# Novo_Container.net
KiCad netlist of a schematic drawn in EAGLE
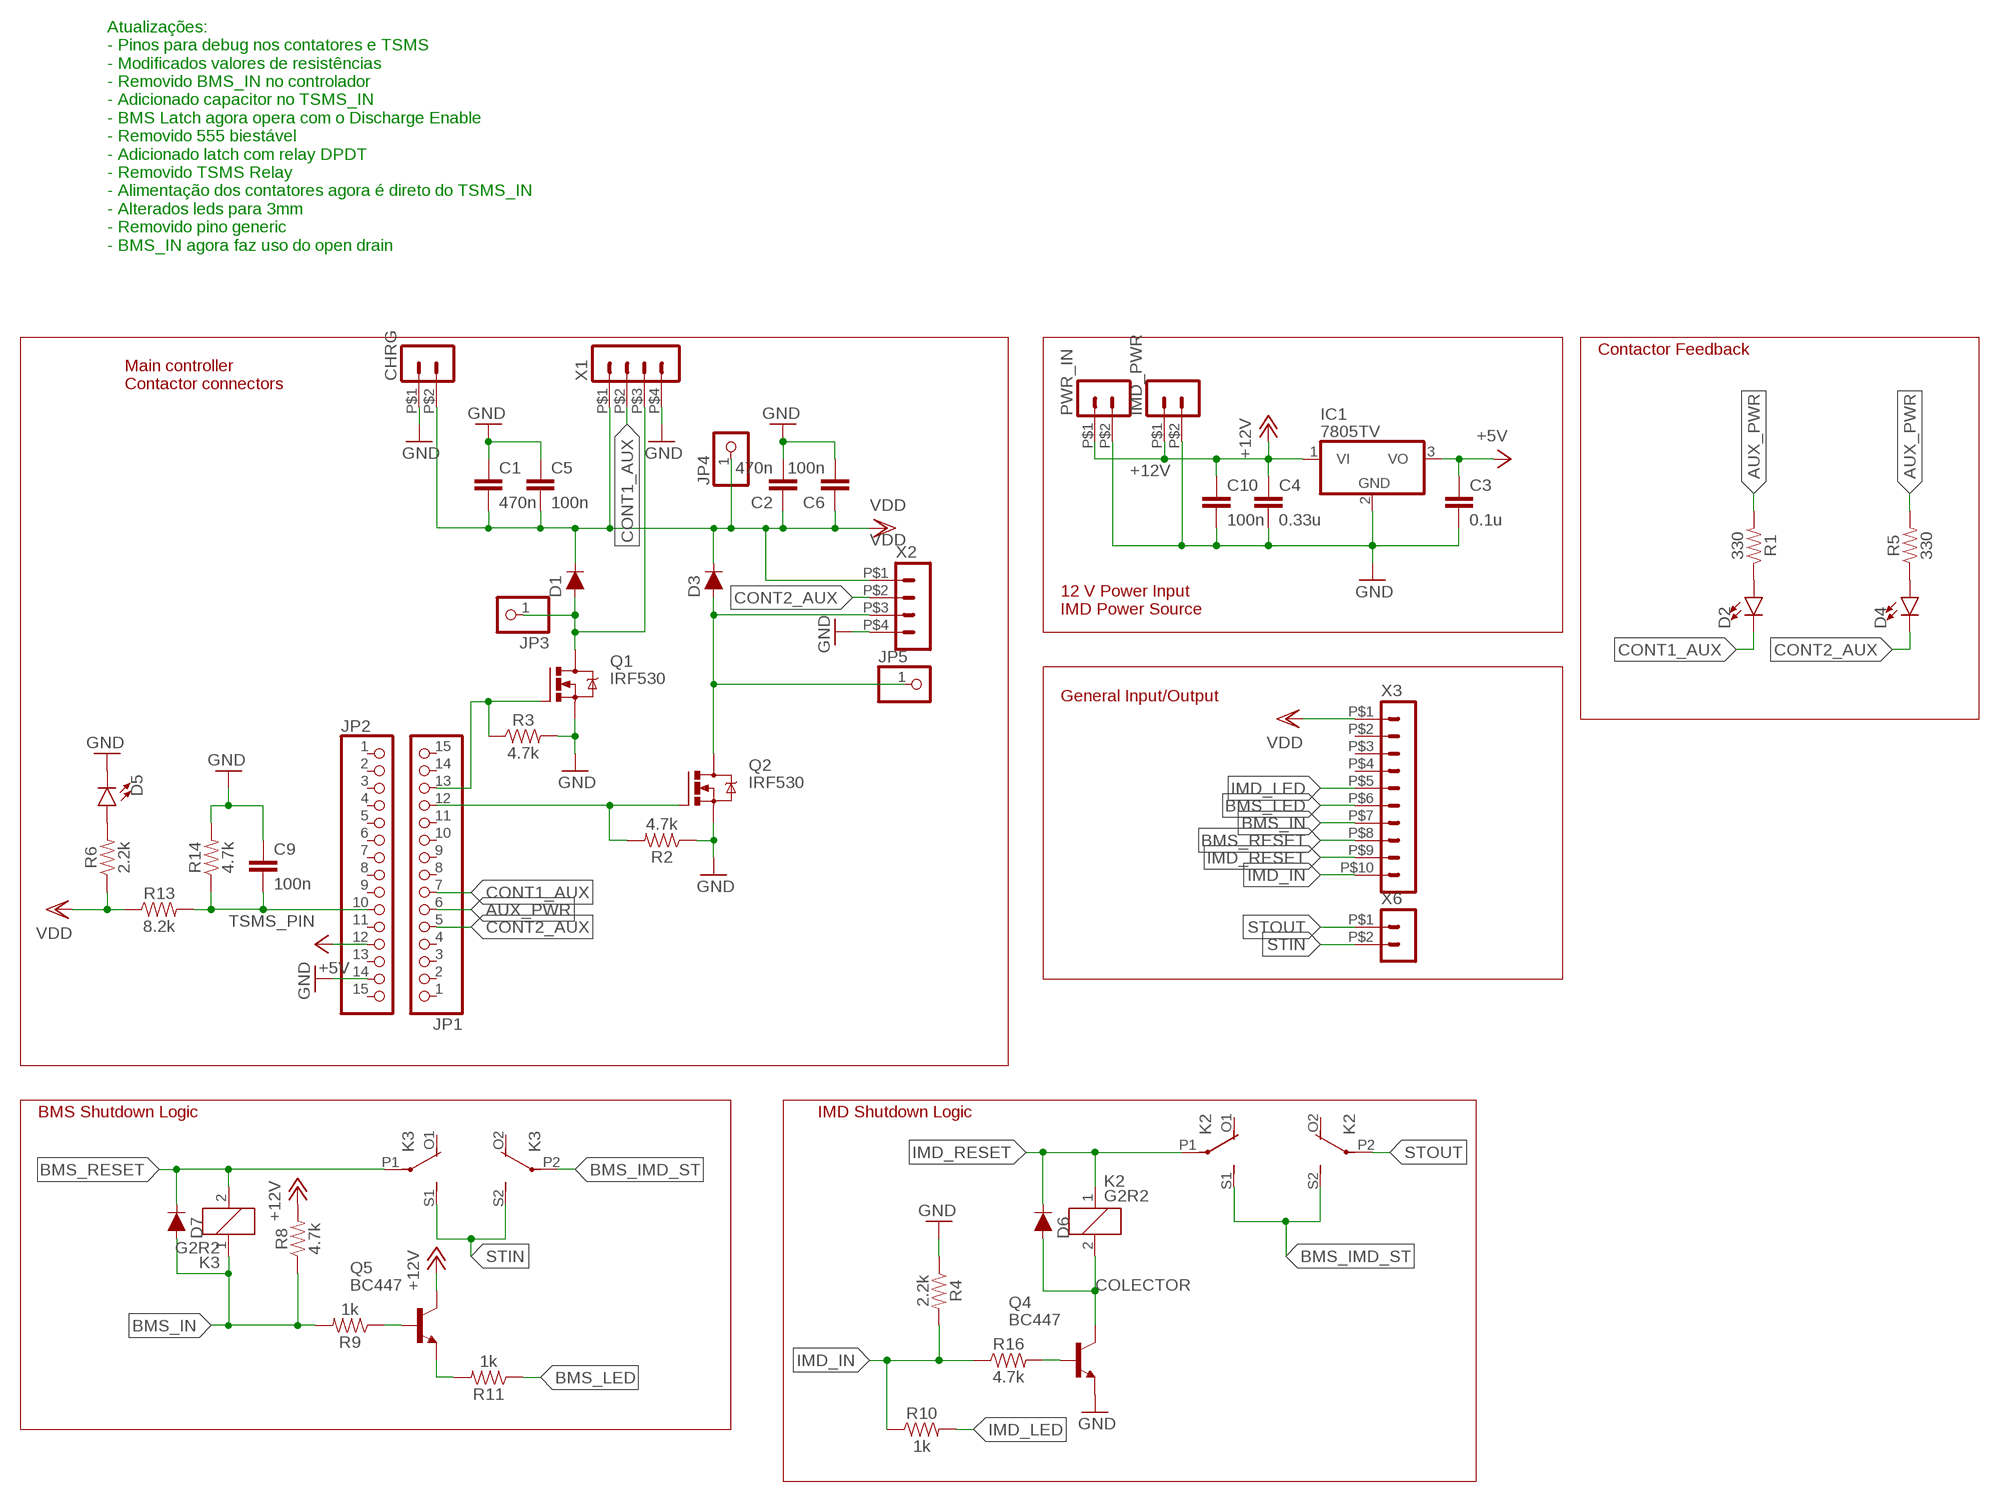
[diagram p0: schematic, sheet 1]

(export (version "E")
  (design (tool "Eeschema 10.0.6"))
  (components
    (comp (ref "C1")
      (value "470n")
      (footprint "eagle-import:C025-025X050")
      (libsource (lib "eagle-import") (part "C-EU025-025X050"))
    )
    (comp (ref "C2")
      (value "470n")
      (footprint "eagle-import:C025-025X050")
      (libsource (lib "eagle-import") (part "C-EU025-025X050"))
    )
    (comp (ref "C3")
      (value "0.1u")
      (footprint "eagle-import:C025-025X050")
      (libsource (lib "eagle-import") (part "C-EU025-025X050"))
    )
    (comp (ref "C4")
      (value "0.33u")
      (footprint "eagle-import:C025-025X050")
      (libsource (lib "eagle-import") (part "C-EU025-025X050"))
    )
    (comp (ref "C5")
      (value "100n")
      (footprint "eagle-import:C025-025X050")
      (libsource (lib "eagle-import") (part "C-EU025-025X050"))
    )
    (comp (ref "C6")
      (value "100n")
      (footprint "eagle-import:C025-025X050")
      (libsource (lib "eagle-import") (part "C-EU025-025X050"))
    )
    (comp (ref "C9")
      (value "100n")
      (footprint "eagle-import:C025-025X050")
      (libsource (lib "eagle-import") (part "C-EU025-025X050"))
    )
    (comp (ref "C10")
      (value "100n")
      (footprint "eagle-import:C025-025X050")
      (libsource (lib "eagle-import") (part "C-EU025-025X050"))
    )
    (comp (ref "CHRG")
      (value "HEADER_POS2_43650-0200")
      (footprint "eagle-import:43650-0200")
      (libsource (lib "eagle-import") (part "HEADER_POS2_?43650-0200"))
    )
    (comp (ref "D1")
      (value "DIODE-1N4148")
      (footprint "eagle-import:DIODE-1N4148")
      (libsource (lib "eagle-import") (part "DIODE-1N4148"))
    )
    (comp (ref "D2")
      (value "LED3MM")
      (footprint "eagle-import:LED_3MM")
      (libsource (lib "eagle-import") (part "LED3MM"))
    )
    (comp (ref "D3")
      (value "DIODE-1N4148")
      (footprint "eagle-import:DIODE-1N4148")
      (libsource (lib "eagle-import") (part "DIODE-1N4148"))
    )
    (comp (ref "D4")
      (value "LED3MM")
      (footprint "eagle-import:LED_3MM")
      (libsource (lib "eagle-import") (part "LED3MM"))
    )
    (comp (ref "D5")
      (value "LED3MM")
      (footprint "eagle-import:LED_3MM")
      (libsource (lib "eagle-import") (part "LED3MM"))
    )
    (comp (ref "D6")
      (value "DIODE-1N4148")
      (footprint "eagle-import:DIODE-1N4148")
      (libsource (lib "eagle-import") (part "DIODE-1N4148"))
    )
    (comp (ref "D7")
      (value "DIODE-1N4148")
      (footprint "eagle-import:DIODE-1N4148")
      (libsource (lib "eagle-import") (part "DIODE-1N4148"))
    )
    (comp (ref "IC1")
      (value "7805TV")
      (footprint "eagle-import:TO220V")
      (libsource (lib "eagle-import") (part "78TV05"))
    )
    (comp (ref "IMD_PWR")
      (value "HEADER_POS2_43650-0200")
      (footprint "eagle-import:43650-0200")
      (libsource (lib "eagle-import") (part "HEADER_POS2_?43650-0200"))
    )
    (comp (ref "JP1")
      (value "PINHD-1X15")
      (footprint "eagle-import:1X15")
      (libsource (lib "eagle-import") (part "PINHD-1X15"))
    )
    (comp (ref "JP2")
      (value "PINHD-1X15")
      (footprint "eagle-import:1X15")
      (libsource (lib "eagle-import") (part "PINHD-1X15"))
    )
    (comp (ref "JP3")
      (value "PINHD-1X1")
      (footprint "eagle-import:1X01")
      (libsource (lib "eagle-import") (part "PINHD-1X1"))
    )
    (comp (ref "JP4")
      (value "PINHD-1X1")
      (footprint "eagle-import:1X01")
      (libsource (lib "eagle-import") (part "PINHD-1X1"))
    )
    (comp (ref "JP5")
      (value "PINHD-1X1")
      (footprint "eagle-import:1X01")
      (libsource (lib "eagle-import") (part "PINHD-1X1"))
    )
    (comp (ref "K2")
      (value "G2R2")
      (footprint "eagle-import:G2R2")
      (fields (field (name "MF") "OMRON COMPONENTS USA") (field (name "MPN") "G2R-2-DC6"))
      (libsource (lib "eagle-import") (part "G2R2"))
    )
    (comp (ref "K3")
      (value "G2R2")
      (footprint "eagle-import:G2R2")
      (fields (field (name "MF") "OMRON COMPONENTS USA") (field (name "MPN") "G2R-2-DC6"))
      (libsource (lib "eagle-import") (part "G2R2"))
    )
    (comp (ref "PWR_IN")
      (value "HEADER_POS2_43650-0200")
      (footprint "eagle-import:43650-0200")
      (libsource (lib "eagle-import") (part "HEADER_POS2_?43650-0200"))
    )
    (comp (ref "Q1")
      (value "IRF530")
      (footprint "eagle-import:TO220BV")
      (libsource (lib "eagle-import") (part "IRF530"))
    )
    (comp (ref "Q2")
      (value "IRF530")
      (footprint "eagle-import:TO220BV")
      (libsource (lib "eagle-import") (part "IRF530"))
    )
    (comp (ref "Q4")
      (value "BC447")
      (footprint "eagle-import:TO92-EBC")
      (libsource (lib "eagle-import") (part "BC447"))
    )
    (comp (ref "Q5")
      (value "BC447")
      (footprint "eagle-import:TO92-EBC")
      (libsource (lib "eagle-import") (part "BC447"))
    )
    (comp (ref "R1")
      (value "330")
      (footprint "eagle-import:AXIAL-0.3")
      (libsource (lib "eagle-import") (part "RESISTORAXIAL-0.3"))
    )
    (comp (ref "R2")
      (value "4.7k")
      (footprint "eagle-import:AXIAL-0.3")
      (libsource (lib "eagle-import") (part "RESISTORAXIAL-0.3"))
    )
    (comp (ref "R3")
      (value "4.7k")
      (footprint "eagle-import:AXIAL-0.3")
      (libsource (lib "eagle-import") (part "RESISTORAXIAL-0.3"))
    )
    (comp (ref "R4")
      (value "2.2k")
      (footprint "eagle-import:AXIAL-0.3")
      (libsource (lib "eagle-import") (part "RESISTORAXIAL-0.3"))
    )
    (comp (ref "R5")
      (value "330")
      (footprint "eagle-import:AXIAL-0.3")
      (libsource (lib "eagle-import") (part "RESISTORAXIAL-0.3"))
    )
    (comp (ref "R6")
      (value "2.2k")
      (footprint "eagle-import:AXIAL-0.3")
      (libsource (lib "eagle-import") (part "RESISTORAXIAL-0.3"))
    )
    (comp (ref "R8")
      (value "4.7k")
      (footprint "eagle-import:AXIAL-0.3")
      (libsource (lib "eagle-import") (part "RESISTORAXIAL-0.3"))
    )
    (comp (ref "R9")
      (value "1k")
      (footprint "eagle-import:AXIAL-0.3")
      (libsource (lib "eagle-import") (part "RESISTORAXIAL-0.3"))
    )
    (comp (ref "R10")
      (value "1k")
      (footprint "eagle-import:AXIAL-0.3")
      (libsource (lib "eagle-import") (part "RESISTORAXIAL-0.3"))
    )
    (comp (ref "R11")
      (value "1k")
      (footprint "eagle-import:AXIAL-0.3")
      (libsource (lib "eagle-import") (part "RESISTORAXIAL-0.3"))
    )
    (comp (ref "R13")
      (value "8.2k")
      (footprint "eagle-import:AXIAL-0.3")
      (libsource (lib "eagle-import") (part "RESISTORAXIAL-0.3"))
    )
    (comp (ref "R14")
      (value "4.7k")
      (footprint "eagle-import:AXIAL-0.3")
      (libsource (lib "eagle-import") (part "RESISTORAXIAL-0.3"))
    )
    (comp (ref "R16")
      (value "4.7k")
      (footprint "eagle-import:AXIAL-0.3")
      (libsource (lib "eagle-import") (part "RESISTORAXIAL-0.3"))
    )
    (comp (ref "X1")
      (value "HEADER_POS4_43045-0401")
      (footprint "eagle-import:43045-0400")
      (libsource (lib "eagle-import") (part "HEADER_POS4_?43045-0401"))
    )
    (comp (ref "X2")
      (value "HEADER_POS4_43045-0401")
      (footprint "eagle-import:43045-0400")
      (libsource (lib "eagle-import") (part "HEADER_POS4_?43045-0401"))
    )
    (comp (ref "X3")
      (value "HEADER_POS10_43045-1000")
      (footprint "eagle-import:43045-1000")
      (libsource (lib "eagle-import") (part "HEADER_POS10_?43045-1000"))
    )
    (comp (ref "X6")
      (value "HEADER_POS2_43650-0200")
      (footprint "eagle-import:43650-0200")
      (libsource (lib "eagle-import") (part "HEADER_POS2_?43650-0200"))
    )
  )
  (nets
    (net (code "1") (name "+5V") (class "Default")
      (node (ref "C3") (pin "1") (pinfunction "1_1") (pintype "passive"))
      (node (ref "IC1") (pin "3") (pinfunction "VO_3") (pintype "passive"))
      (node (ref "JP2") (pin "12") (pinfunction "12_12") (pintype "passive"))
    )
    (net (code "2") (name "+12V") (class "Default")
      (node (ref "C10") (pin "1") (pinfunction "1_1") (pintype "passive"))
      (node (ref "C4") (pin "1") (pinfunction "1_1") (pintype "passive"))
      (node (ref "IC1") (pin "1") (pinfunction "VI_1") (pintype "input"))
      (node (ref "IMD_PWR") (pin "P$1") (pinfunction "1_P$1") (pintype "passive"))
      (node (ref "PWR_IN") (pin "P$1") (pinfunction "1_P$1") (pintype "passive"))
      (node (ref "Q5") (pin "C") (pinfunction "C_C") (pintype "passive"))
      (node (ref "R8") (pin "P$2") (pinfunction "2_P$2") (pintype "passive"))
    )
    (net (code "3") (name "/COLECTOR") (class "Default")
      (node (ref "D6") (pin "A") (pinfunction "A_A") (pintype "passive"))
      (node (ref "K2") (pin "2") (pinfunction "2_2") (pintype "passive"))
      (node (ref "Q4") (pin "C") (pinfunction "C_C") (pintype "passive"))
    )
    (net (code "4") (name "/TSMS_PIN") (class "Default")
      (node (ref "C9") (pin "2") (pinfunction "2_2") (pintype "passive"))
      (node (ref "JP2") (pin "10") (pinfunction "10_10") (pintype "passive"))
      (node (ref "R13") (pin "P$2") (pinfunction "2_P$2") (pintype "passive"))
      (node (ref "R14") (pin "P$1") (pinfunction "1_P$1") (pintype "passive"))
    )
    (net (code "5") (name "AUX_PWR") (class "Default")
      (node (ref "JP1") (pin "6") (pinfunction "6_6") (pintype "passive"))
      (node (ref "R1") (pin "P$2") (pinfunction "2_P$2") (pintype "passive"))
      (node (ref "R5") (pin "P$2") (pinfunction "2_P$2") (pintype "passive"))
    )
    (net (code "6") (name "BMS_IMD_ST") (class "Default")
      (node (ref "K2") (pin "S1") (pinfunction "S_S1") (pintype "passive"))
      (node (ref "K2") (pin "S2") (pinfunction "S_S2") (pintype "passive"))
      (node (ref "K3") (pin "P2") (pinfunction "P_P2") (pintype "passive"))
    )
    (net (code "7") (name "BMS_IN") (class "Default")
      (node (ref "D7") (pin "A") (pinfunction "A_A") (pintype "passive"))
      (node (ref "K3") (pin "1") (pinfunction "1_1") (pintype "passive"))
      (node (ref "R8") (pin "P$1") (pinfunction "1_P$1") (pintype "passive"))
      (node (ref "R9") (pin "P$2") (pinfunction "2_P$2") (pintype "passive"))
      (node (ref "X3") (pin "P$7") (pinfunction "7_P$7") (pintype "passive"))
    )
    (net (code "8") (name "BMS_LED") (class "Default")
      (node (ref "R11") (pin "P$1") (pinfunction "1_P$1") (pintype "passive"))
      (node (ref "X3") (pin "P$6") (pinfunction "6_P$6") (pintype "passive"))
    )
    (net (code "9") (name "BMS_RESET") (class "Default")
      (node (ref "D7") (pin "C") (pinfunction "C_C") (pintype "passive"))
      (node (ref "K3") (pin "2") (pinfunction "2_2") (pintype "passive"))
      (node (ref "K3") (pin "P1") (pinfunction "P_P1") (pintype "passive"))
      (node (ref "X3") (pin "P$8") (pinfunction "8_P$8") (pintype "passive"))
    )
    (net (code "10") (name "CONT1_AUX") (class "Default")
      (node (ref "D2") (pin "K") (pinfunction "C_K") (pintype "passive"))
      (node (ref "JP1") (pin "7") (pinfunction "7_7") (pintype "passive"))
      (node (ref "X1") (pin "P$2") (pinfunction "2_P$2") (pintype "passive"))
    )
    (net (code "11") (name "CONT2_AUX") (class "Default")
      (node (ref "D4") (pin "K") (pinfunction "C_K") (pintype "passive"))
      (node (ref "JP1") (pin "5") (pinfunction "5_5") (pintype "passive"))
      (node (ref "X2") (pin "P$2") (pinfunction "2_P$2") (pintype "passive"))
    )
    (net (code "12") (name "GND") (class "Default")
      (node (ref "C1") (pin "1") (pinfunction "1_1") (pintype "passive"))
      (node (ref "C10") (pin "2") (pinfunction "2_2") (pintype "passive"))
      (node (ref "C2") (pin "2") (pinfunction "2_2") (pintype "passive"))
      (node (ref "C3") (pin "2") (pinfunction "2_2") (pintype "passive"))
      (node (ref "C4") (pin "2") (pinfunction "2_2") (pintype "passive"))
      (node (ref "C5") (pin "1") (pinfunction "1_1") (pintype "passive"))
      (node (ref "C6") (pin "2") (pinfunction "2_2") (pintype "passive"))
      (node (ref "C9") (pin "1") (pinfunction "1_1") (pintype "passive"))
      (node (ref "CHRG") (pin "P$1") (pinfunction "1_P$1") (pintype "passive"))
      (node (ref "D5") (pin "K") (pinfunction "C_K") (pintype "passive"))
      (node (ref "IC1") (pin "2") (pinfunction "GND_2") (pintype "passive"))
      (node (ref "IMD_PWR") (pin "P$2") (pinfunction "2_P$2") (pintype "passive"))
      (node (ref "JP2") (pin "14") (pinfunction "14_14") (pintype "passive"))
      (node (ref "PWR_IN") (pin "P$2") (pinfunction "2_P$2") (pintype "passive"))
      (node (ref "Q1") (pin "S") (pinfunction "S_S") (pintype "passive"))
      (node (ref "Q2") (pin "S") (pinfunction "S_S") (pintype "passive"))
      (node (ref "Q4") (pin "E") (pinfunction "E_E") (pintype "passive"))
      (node (ref "R14") (pin "P$2") (pinfunction "2_P$2") (pintype "passive"))
      (node (ref "R2") (pin "P$1") (pinfunction "1_P$1") (pintype "passive"))
      (node (ref "R3") (pin "P$2") (pinfunction "2_P$2") (pintype "passive"))
      (node (ref "R4") (pin "P$1") (pinfunction "1_P$1") (pintype "passive"))
      (node (ref "X1") (pin "P$4") (pinfunction "4_P$4") (pintype "passive"))
      (node (ref "X2") (pin "P$4") (pinfunction "4_P$4") (pintype "passive"))
    )
    (net (code "13") (name "IMD_IN") (class "Default")
      (node (ref "R10") (pin "P$1") (pinfunction "1_P$1") (pintype "passive"))
      (node (ref "R16") (pin "P$1") (pinfunction "1_P$1") (pintype "passive"))
      (node (ref "R4") (pin "P$2") (pinfunction "2_P$2") (pintype "passive"))
      (node (ref "X3") (pin "P$10") (pinfunction "10_P$10") (pintype "passive"))
    )
    (net (code "14") (name "IMD_LED") (class "Default")
      (node (ref "R10") (pin "P$2") (pinfunction "2_P$2") (pintype "passive"))
      (node (ref "X3") (pin "P$5") (pinfunction "5_P$5") (pintype "passive"))
    )
    (net (code "15") (name "IMD_RESET") (class "Default")
      (node (ref "D6") (pin "C") (pinfunction "C_C") (pintype "passive"))
      (node (ref "K2") (pin "1") (pinfunction "1_1") (pintype "passive"))
      (node (ref "K2") (pin "P1") (pinfunction "P_P1") (pintype "passive"))
      (node (ref "X3") (pin "P$9") (pinfunction "9_P$9") (pintype "passive"))
    )
    (net (code "16") (name "Net-(R1-1)") (class "Default")
      (node (ref "D2") (pin "A") (pinfunction "A_A") (pintype "passive"))
      (node (ref "R1") (pin "P$1") (pinfunction "1_P$1") (pintype "passive"))
    )
    (net (code "17") (name "Net-(R2-2)") (class "Default")
      (node (ref "JP1") (pin "12") (pinfunction "12_12") (pintype "passive"))
      (node (ref "Q2") (pin "G") (pinfunction "G_G") (pintype "passive"))
      (node (ref "R2") (pin "P$2") (pinfunction "2_P$2") (pintype "passive"))
    )
    (net (code "18") (name "Net-(R3-1)") (class "Default")
      (node (ref "JP1") (pin "13") (pinfunction "13_13") (pintype "passive"))
      (node (ref "Q1") (pin "G") (pinfunction "G_G") (pintype "passive"))
      (node (ref "R3") (pin "P$1") (pinfunction "1_P$1") (pintype "passive"))
    )
    (net (code "19") (name "Net-(R5-1)") (class "Default")
      (node (ref "D4") (pin "A") (pinfunction "A_A") (pintype "passive"))
      (node (ref "R5") (pin "P$1") (pinfunction "1_P$1") (pintype "passive"))
    )
    (net (code "20") (name "Net-(R6-2)") (class "Default")
      (node (ref "D5") (pin "A") (pinfunction "A_A") (pintype "passive"))
      (node (ref "R6") (pin "P$2") (pinfunction "2_P$2") (pintype "passive"))
    )
    (net (code "21") (name "Net-(R9-1)") (class "Default")
      (node (ref "Q5") (pin "B") (pinfunction "B_B") (pintype "passive"))
      (node (ref "R9") (pin "P$1") (pinfunction "1_P$1") (pintype "passive"))
    )
    (net (code "22") (name "Net-(R11-2)") (class "Default")
      (node (ref "Q5") (pin "E") (pinfunction "E_E") (pintype "passive"))
      (node (ref "R11") (pin "P$2") (pinfunction "2_P$2") (pintype "passive"))
    )
    (net (code "23") (name "Net-(R16-2)") (class "Default")
      (node (ref "Q4") (pin "B") (pinfunction "B_B") (pintype "passive"))
      (node (ref "R16") (pin "P$2") (pinfunction "2_P$2") (pintype "passive"))
    )
    (net (code "24") (name "Net-(X1-3)") (class "Default")
      (node (ref "D1") (pin "A") (pinfunction "A_A") (pintype "passive"))
      (node (ref "JP3") (pin "1") (pinfunction "1_1") (pintype "passive"))
      (node (ref "Q1") (pin "D") (pinfunction "D_D") (pintype "passive"))
      (node (ref "X1") (pin "P$3") (pinfunction "3_P$3") (pintype "passive"))
    )
    (net (code "25") (name "Net-(X2-3)") (class "Default")
      (node (ref "D3") (pin "A") (pinfunction "A_A") (pintype "passive"))
      (node (ref "JP5") (pin "1") (pinfunction "1_1") (pintype "passive"))
      (node (ref "Q2") (pin "D") (pinfunction "D_D") (pintype "passive"))
      (node (ref "X2") (pin "P$3") (pinfunction "3_P$3") (pintype "passive"))
    )
    (net (code "26") (name "STIN") (class "Default")
      (node (ref "K3") (pin "S1") (pinfunction "S_S1") (pintype "passive"))
      (node (ref "K3") (pin "S2") (pinfunction "S_S2") (pintype "passive"))
      (node (ref "X6") (pin "P$2") (pinfunction "2_P$2") (pintype "passive"))
    )
    (net (code "27") (name "STOUT") (class "Default")
      (node (ref "K2") (pin "P2") (pinfunction "P_P2") (pintype "passive"))
      (node (ref "X6") (pin "P$1") (pinfunction "1_P$1") (pintype "passive"))
    )
    (net (code "28") (name "VDD") (class "Default")
      (node (ref "C1") (pin "2") (pinfunction "2_2") (pintype "passive"))
      (node (ref "C2") (pin "1") (pinfunction "1_1") (pintype "passive"))
      (node (ref "C5") (pin "2") (pinfunction "2_2") (pintype "passive"))
      (node (ref "C6") (pin "1") (pinfunction "1_1") (pintype "passive"))
      (node (ref "CHRG") (pin "P$2") (pinfunction "2_P$2") (pintype "passive"))
      (node (ref "D1") (pin "C") (pinfunction "C_C") (pintype "passive"))
      (node (ref "D3") (pin "C") (pinfunction "C_C") (pintype "passive"))
      (node (ref "JP4") (pin "1") (pinfunction "1_1") (pintype "passive"))
      (node (ref "R13") (pin "P$1") (pinfunction "1_P$1") (pintype "passive"))
      (node (ref "R6") (pin "P$1") (pinfunction "1_P$1") (pintype "passive"))
      (node (ref "X1") (pin "P$1") (pinfunction "1_P$1") (pintype "passive"))
      (node (ref "X2") (pin "P$1") (pinfunction "1_P$1") (pintype "passive"))
      (node (ref "X3") (pin "P$1") (pinfunction "1_P$1") (pintype "passive"))
    )
    (net (code "29") (name "unconnected-(JP1-Pad1)") (class "Default")
      (node (ref "JP1") (pin "1") (pinfunction "1_1") (pintype "passive"))
    )
    (net (code "30") (name "unconnected-(JP1-Pad2)") (class "Default")
      (node (ref "JP1") (pin "2") (pinfunction "2_2") (pintype "passive"))
    )
    (net (code "31") (name "unconnected-(JP1-Pad3)") (class "Default")
      (node (ref "JP1") (pin "3") (pinfunction "3_3") (pintype "passive"))
    )
    (net (code "32") (name "unconnected-(JP1-Pad4)") (class "Default")
      (node (ref "JP1") (pin "4") (pinfunction "4_4") (pintype "passive"))
    )
    (net (code "33") (name "unconnected-(JP1-Pad8)") (class "Default")
      (node (ref "JP1") (pin "8") (pinfunction "8_8") (pintype "passive"))
    )
    (net (code "34") (name "unconnected-(JP1-Pad9)") (class "Default")
      (node (ref "JP1") (pin "9") (pinfunction "9_9") (pintype "passive"))
    )
    (net (code "35") (name "unconnected-(JP1-Pad10)") (class "Default")
      (node (ref "JP1") (pin "10") (pinfunction "10_10") (pintype "passive"))
    )
    (net (code "36") (name "unconnected-(JP1-Pad11)") (class "Default")
      (node (ref "JP1") (pin "11") (pinfunction "11_11") (pintype "passive"))
    )
    (net (code "37") (name "unconnected-(JP1-Pad14)") (class "Default")
      (node (ref "JP1") (pin "14") (pinfunction "14_14") (pintype "passive"))
    )
    (net (code "38") (name "unconnected-(JP1-Pad15)") (class "Default")
      (node (ref "JP1") (pin "15") (pinfunction "15_15") (pintype "passive"))
    )
    (net (code "39") (name "unconnected-(JP2-Pad1)") (class "Default")
      (node (ref "JP2") (pin "1") (pinfunction "1_1") (pintype "passive"))
    )
    (net (code "40") (name "unconnected-(JP2-Pad2)") (class "Default")
      (node (ref "JP2") (pin "2") (pinfunction "2_2") (pintype "passive"))
    )
    (net (code "41") (name "unconnected-(JP2-Pad3)") (class "Default")
      (node (ref "JP2") (pin "3") (pinfunction "3_3") (pintype "passive"))
    )
    (net (code "42") (name "unconnected-(JP2-Pad4)") (class "Default")
      (node (ref "JP2") (pin "4") (pinfunction "4_4") (pintype "passive"))
    )
    (net (code "43") (name "unconnected-(JP2-Pad5)") (class "Default")
      (node (ref "JP2") (pin "5") (pinfunction "5_5") (pintype "passive"))
    )
    (net (code "44") (name "unconnected-(JP2-Pad6)") (class "Default")
      (node (ref "JP2") (pin "6") (pinfunction "6_6") (pintype "passive"))
    )
    (net (code "45") (name "unconnected-(JP2-Pad7)") (class "Default")
      (node (ref "JP2") (pin "7") (pinfunction "7_7") (pintype "passive"))
    )
    (net (code "46") (name "unconnected-(JP2-Pad8)") (class "Default")
      (node (ref "JP2") (pin "8") (pinfunction "8_8") (pintype "passive"))
    )
    (net (code "47") (name "unconnected-(JP2-Pad9)") (class "Default")
      (node (ref "JP2") (pin "9") (pinfunction "9_9") (pintype "passive"))
    )
    (net (code "48") (name "unconnected-(JP2-Pad11)") (class "Default")
      (node (ref "JP2") (pin "11") (pinfunction "11_11") (pintype "passive"))
    )
    (net (code "49") (name "unconnected-(JP2-Pad13)") (class "Default")
      (node (ref "JP2") (pin "13") (pinfunction "13_13") (pintype "passive"))
    )
    (net (code "50") (name "unconnected-(JP2-Pad15)") (class "Default")
      (node (ref "JP2") (pin "15") (pinfunction "15_15") (pintype "passive"))
    )
    (net (code "51") (name "unconnected-(K2B-O-PadO1)") (class "Default")
      (node (ref "K2") (pin "O1") (pinfunction "O_O1") (pintype "passive"))
    )
    (net (code "52") (name "unconnected-(K2C-O-PadO2)") (class "Default")
      (node (ref "K2") (pin "O2") (pinfunction "O_O2") (pintype "passive"))
    )
    (net (code "53") (name "unconnected-(K3B-O-PadO1)") (class "Default")
      (node (ref "K3") (pin "O1") (pinfunction "O_O1") (pintype "passive"))
    )
    (net (code "54") (name "unconnected-(K3C-O-PadO2)") (class "Default")
      (node (ref "K3") (pin "O2") (pinfunction "O_O2") (pintype "passive"))
    )
    (net (code "55") (name "unconnected-(X3-2-PadP$2)") (class "Default")
      (node (ref "X3") (pin "P$2") (pinfunction "2_P$2") (pintype "passive"))
    )
    (net (code "56") (name "unconnected-(X3-3-PadP$3)") (class "Default")
      (node (ref "X3") (pin "P$3") (pinfunction "3_P$3") (pintype "passive"))
    )
    (net (code "57") (name "unconnected-(X3-4-PadP$4)") (class "Default")
      (node (ref "X3") (pin "P$4") (pinfunction "4_P$4") (pintype "passive"))
    )
  )
)
